# DecadeBox_2.net
KiCad netlist of a schematic drawn in Altium Designer
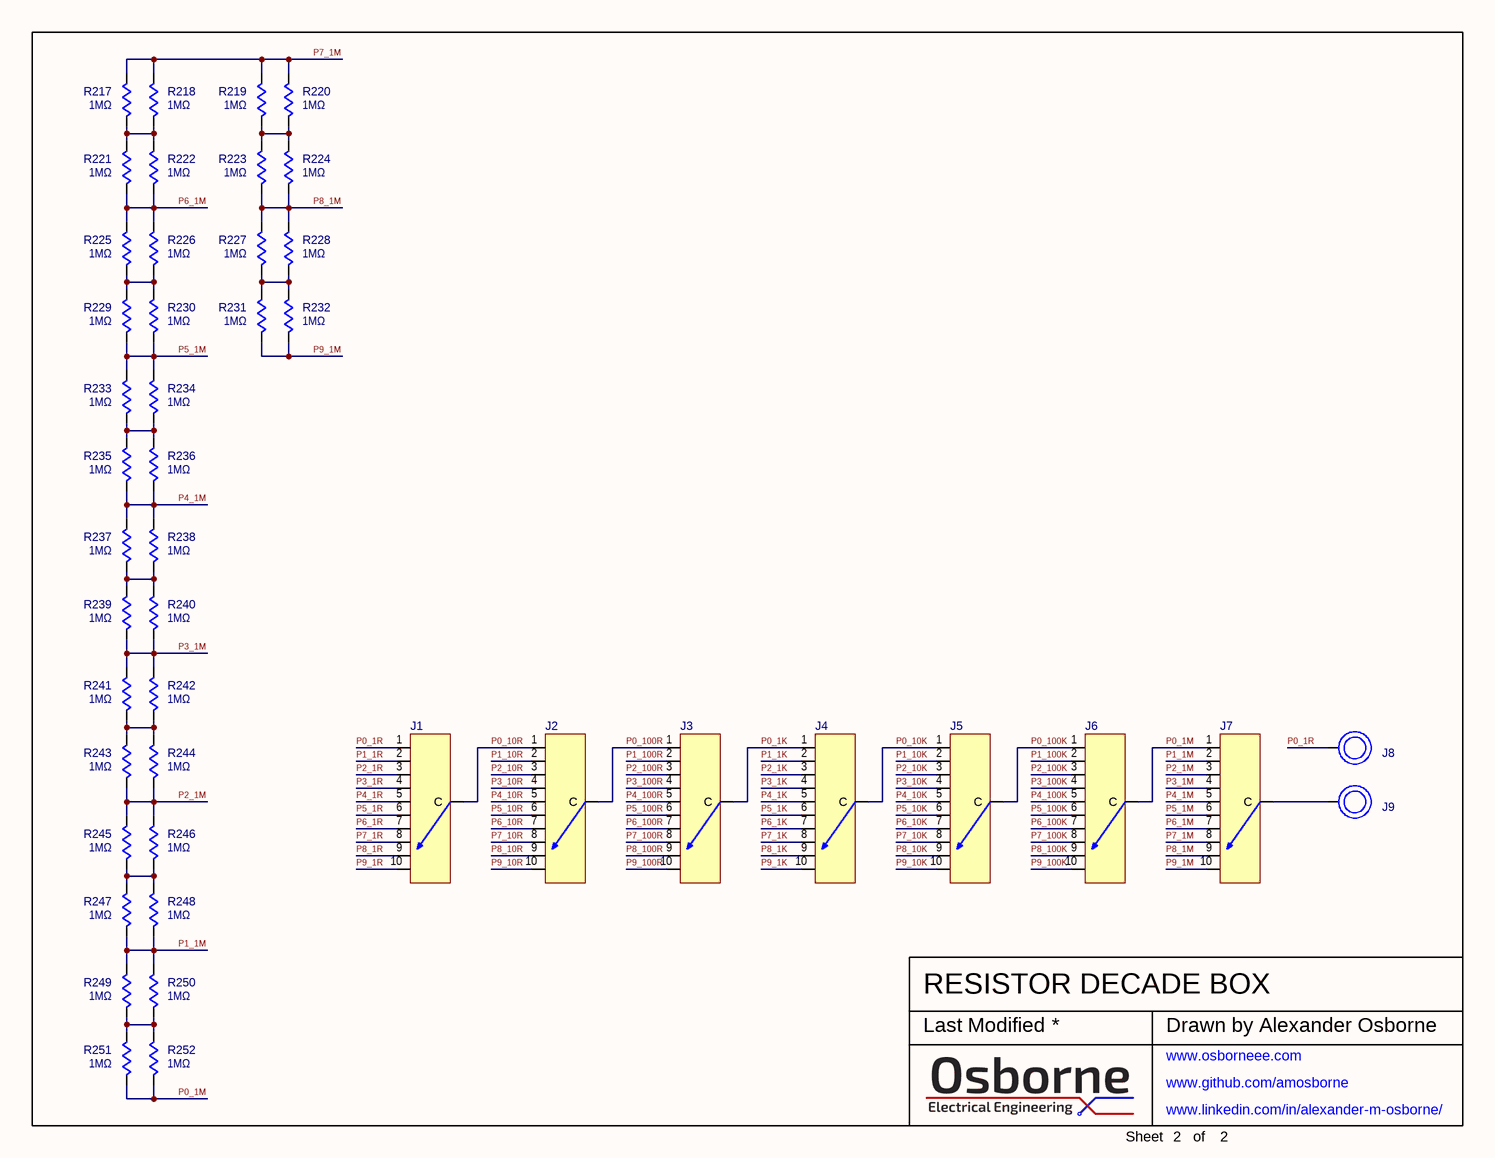
[diagram p0: DecadeBox_2.SchDoc]

(export (version "E")
  (design (tool "Eeschema 10.0.6"))
  (components
    (comp (ref "J1")
      (value "706-56BDP36-01PAJS")
      (footprint "ROTARY")
      (description "10 POLE, SINGLE THROW, ROTARY SWITCH")
      (libsource (lib "DecadeBox") (part "ROTARY"))
    )
    (comp (ref "J2")
      (value "706-56BDP36-01PAJS")
      (footprint "ROTARY")
      (description "10 POLE, SINGLE THROW, ROTARY SWITCH")
      (libsource (lib "DecadeBox") (part "ROTARY"))
    )
    (comp (ref "J3")
      (value "706-56BDP36-01PAJS")
      (footprint "ROTARY")
      (description "10 POLE, SINGLE THROW, ROTARY SWITCH")
      (libsource (lib "DecadeBox") (part "ROTARY"))
    )
    (comp (ref "J4")
      (value "706-56BDP36-01PAJS")
      (footprint "ROTARY")
      (description "10 POLE, SINGLE THROW, ROTARY SWITCH")
      (libsource (lib "DecadeBox") (part "ROTARY"))
    )
    (comp (ref "J5")
      (value "706-56BDP36-01PAJS")
      (footprint "ROTARY")
      (description "10 POLE, SINGLE THROW, ROTARY SWITCH")
      (libsource (lib "DecadeBox") (part "ROTARY"))
    )
    (comp (ref "J6")
      (value "706-56BDP36-01PAJS")
      (footprint "ROTARY")
      (description "10 POLE, SINGLE THROW, ROTARY SWITCH")
      (libsource (lib "DecadeBox") (part "ROTARY"))
    )
    (comp (ref "J7")
      (value "706-56BDP36-01PAJS")
      (footprint "ROTARY")
      (description "10 POLE, SINGLE THROW, ROTARY SWITCH")
      (libsource (lib "DecadeBox") (part "ROTARY"))
    )
    (comp (ref "J8")
      (value "BINDING")
      (description "BINDING POST")
      (libsource (lib "DecadeBox") (part "BINDING"))
    )
    (comp (ref "J9")
      (value "BINDING")
      (description "BINDING POST")
      (libsource (lib "DecadeBox") (part "BINDING"))
    )
    (comp (ref "R217")
      (value "1MΩ")
      (footprint "MRS25")
      (description "RES 1MΩ 1% 50ppm/K 600mW")
      (fields (field (name "TOLERANCE") "1% + 50ppm/K") (field (name "POWER") "600mW"))
      (libsource (lib "DecadeBox") (part "RES-1MOHM"))
    )
    (comp (ref "R218")
      (value "1MΩ")
      (footprint "MRS25")
      (description "RES 1MΩ 1% 50ppm/K 600mW")
      (fields (field (name "TOLERANCE") "1% + 50ppm/K") (field (name "POWER") "600mW"))
      (libsource (lib "DecadeBox") (part "RES-1MOHM"))
    )
    (comp (ref "R219")
      (value "1MΩ")
      (footprint "MRS25")
      (description "RES 1MΩ 1% 50ppm/K 600mW")
      (fields (field (name "TOLERANCE") "1% + 50ppm/K") (field (name "POWER") "600mW"))
      (libsource (lib "DecadeBox") (part "RES-1MOHM"))
    )
    (comp (ref "R220")
      (value "1MΩ")
      (footprint "MRS25")
      (description "RES 1MΩ 1% 50ppm/K 600mW")
      (fields (field (name "TOLERANCE") "1% + 50ppm/K") (field (name "POWER") "600mW"))
      (libsource (lib "DecadeBox") (part "RES-1MOHM"))
    )
    (comp (ref "R221")
      (value "1MΩ")
      (footprint "MRS25")
      (description "RES 1MΩ 1% 50ppm/K 600mW")
      (fields (field (name "TOLERANCE") "1% + 50ppm/K") (field (name "POWER") "600mW"))
      (libsource (lib "DecadeBox") (part "RES-1MOHM"))
    )
    (comp (ref "R222")
      (value "1MΩ")
      (footprint "MRS25")
      (description "RES 1MΩ 1% 50ppm/K 600mW")
      (fields (field (name "TOLERANCE") "1% + 50ppm/K") (field (name "POWER") "600mW"))
      (libsource (lib "DecadeBox") (part "RES-1MOHM"))
    )
    (comp (ref "R223")
      (value "1MΩ")
      (footprint "MRS25")
      (description "RES 1MΩ 1% 50ppm/K 600mW")
      (fields (field (name "TOLERANCE") "1% + 50ppm/K") (field (name "POWER") "600mW"))
      (libsource (lib "DecadeBox") (part "RES-1MOHM"))
    )
    (comp (ref "R224")
      (value "1MΩ")
      (footprint "MRS25")
      (description "RES 1MΩ 1% 50ppm/K 600mW")
      (fields (field (name "TOLERANCE") "1% + 50ppm/K") (field (name "POWER") "600mW"))
      (libsource (lib "DecadeBox") (part "RES-1MOHM"))
    )
    (comp (ref "R225")
      (value "1MΩ")
      (footprint "MRS25")
      (description "RES 1MΩ 1% 50ppm/K 600mW")
      (fields (field (name "TOLERANCE") "1% + 50ppm/K") (field (name "POWER") "600mW"))
      (libsource (lib "DecadeBox") (part "RES-1MOHM"))
    )
    (comp (ref "R226")
      (value "1MΩ")
      (footprint "MRS25")
      (description "RES 1MΩ 1% 50ppm/K 600mW")
      (fields (field (name "TOLERANCE") "1% + 50ppm/K") (field (name "POWER") "600mW"))
      (libsource (lib "DecadeBox") (part "RES-1MOHM"))
    )
    (comp (ref "R227")
      (value "1MΩ")
      (footprint "MRS25")
      (description "RES 1MΩ 1% 50ppm/K 600mW")
      (fields (field (name "TOLERANCE") "1% + 50ppm/K") (field (name "POWER") "600mW"))
      (libsource (lib "DecadeBox") (part "RES-1MOHM"))
    )
    (comp (ref "R228")
      (value "1MΩ")
      (footprint "MRS25")
      (description "RES 1MΩ 1% 50ppm/K 600mW")
      (fields (field (name "TOLERANCE") "1% + 50ppm/K") (field (name "POWER") "600mW"))
      (libsource (lib "DecadeBox") (part "RES-1MOHM"))
    )
    (comp (ref "R229")
      (value "1MΩ")
      (footprint "MRS25")
      (description "RES 1MΩ 1% 50ppm/K 600mW")
      (fields (field (name "TOLERANCE") "1% + 50ppm/K") (field (name "POWER") "600mW"))
      (libsource (lib "DecadeBox") (part "RES-1MOHM"))
    )
    (comp (ref "R230")
      (value "1MΩ")
      (footprint "MRS25")
      (description "RES 1MΩ 1% 50ppm/K 600mW")
      (fields (field (name "TOLERANCE") "1% + 50ppm/K") (field (name "POWER") "600mW"))
      (libsource (lib "DecadeBox") (part "RES-1MOHM"))
    )
    (comp (ref "R231")
      (value "1MΩ")
      (footprint "MRS25")
      (description "RES 1MΩ 1% 50ppm/K 600mW")
      (fields (field (name "TOLERANCE") "1% + 50ppm/K") (field (name "POWER") "600mW"))
      (libsource (lib "DecadeBox") (part "RES-1MOHM"))
    )
    (comp (ref "R232")
      (value "1MΩ")
      (footprint "MRS25")
      (description "RES 1MΩ 1% 50ppm/K 600mW")
      (fields (field (name "TOLERANCE") "1% + 50ppm/K") (field (name "POWER") "600mW"))
      (libsource (lib "DecadeBox") (part "RES-1MOHM"))
    )
    (comp (ref "R233")
      (value "1MΩ")
      (footprint "MRS25")
      (description "RES 1MΩ 1% 50ppm/K 600mW")
      (fields (field (name "TOLERANCE") "1% + 50ppm/K") (field (name "POWER") "600mW"))
      (libsource (lib "DecadeBox") (part "RES-1MOHM"))
    )
    (comp (ref "R234")
      (value "1MΩ")
      (footprint "MRS25")
      (description "RES 1MΩ 1% 50ppm/K 600mW")
      (fields (field (name "TOLERANCE") "1% + 50ppm/K") (field (name "POWER") "600mW"))
      (libsource (lib "DecadeBox") (part "RES-1MOHM"))
    )
    (comp (ref "R235")
      (value "1MΩ")
      (footprint "MRS25")
      (description "RES 1MΩ 1% 50ppm/K 600mW")
      (fields (field (name "TOLERANCE") "1% + 50ppm/K") (field (name "POWER") "600mW"))
      (libsource (lib "DecadeBox") (part "RES-1MOHM"))
    )
    (comp (ref "R236")
      (value "1MΩ")
      (footprint "MRS25")
      (description "RES 1MΩ 1% 50ppm/K 600mW")
      (fields (field (name "TOLERANCE") "1% + 50ppm/K") (field (name "POWER") "600mW"))
      (libsource (lib "DecadeBox") (part "RES-1MOHM"))
    )
    (comp (ref "R237")
      (value "1MΩ")
      (footprint "MRS25")
      (description "RES 1MΩ 1% 50ppm/K 600mW")
      (fields (field (name "TOLERANCE") "1% + 50ppm/K") (field (name "POWER") "600mW"))
      (libsource (lib "DecadeBox") (part "RES-1MOHM"))
    )
    (comp (ref "R238")
      (value "1MΩ")
      (footprint "MRS25")
      (description "RES 1MΩ 1% 50ppm/K 600mW")
      (fields (field (name "TOLERANCE") "1% + 50ppm/K") (field (name "POWER") "600mW"))
      (libsource (lib "DecadeBox") (part "RES-1MOHM"))
    )
    (comp (ref "R239")
      (value "1MΩ")
      (footprint "MRS25")
      (description "RES 1MΩ 1% 50ppm/K 600mW")
      (fields (field (name "TOLERANCE") "1% + 50ppm/K") (field (name "POWER") "600mW"))
      (libsource (lib "DecadeBox") (part "RES-1MOHM"))
    )
    (comp (ref "R240")
      (value "1MΩ")
      (footprint "MRS25")
      (description "RES 1MΩ 1% 50ppm/K 600mW")
      (fields (field (name "TOLERANCE") "1% + 50ppm/K") (field (name "POWER") "600mW"))
      (libsource (lib "DecadeBox") (part "RES-1MOHM"))
    )
    (comp (ref "R241")
      (value "1MΩ")
      (footprint "MRS25")
      (description "RES 1MΩ 1% 50ppm/K 600mW")
      (fields (field (name "TOLERANCE") "1% + 50ppm/K") (field (name "POWER") "600mW"))
      (libsource (lib "DecadeBox") (part "RES-1MOHM"))
    )
    (comp (ref "R242")
      (value "1MΩ")
      (footprint "MRS25")
      (description "RES 1MΩ 1% 50ppm/K 600mW")
      (fields (field (name "TOLERANCE") "1% + 50ppm/K") (field (name "POWER") "600mW"))
      (libsource (lib "DecadeBox") (part "RES-1MOHM"))
    )
    (comp (ref "R243")
      (value "1MΩ")
      (footprint "MRS25")
      (description "RES 1MΩ 1% 50ppm/K 600mW")
      (fields (field (name "TOLERANCE") "1% + 50ppm/K") (field (name "POWER") "600mW"))
      (libsource (lib "DecadeBox") (part "RES-1MOHM"))
    )
    (comp (ref "R244")
      (value "1MΩ")
      (footprint "MRS25")
      (description "RES 1MΩ 1% 50ppm/K 600mW")
      (fields (field (name "TOLERANCE") "1% + 50ppm/K") (field (name "POWER") "600mW"))
      (libsource (lib "DecadeBox") (part "RES-1MOHM"))
    )
    (comp (ref "R245")
      (value "1MΩ")
      (footprint "MRS25")
      (description "RES 1MΩ 1% 50ppm/K 600mW")
      (fields (field (name "TOLERANCE") "1% + 50ppm/K") (field (name "POWER") "600mW"))
      (libsource (lib "DecadeBox") (part "RES-1MOHM"))
    )
    (comp (ref "R246")
      (value "1MΩ")
      (footprint "MRS25")
      (description "RES 1MΩ 1% 50ppm/K 600mW")
      (fields (field (name "TOLERANCE") "1% + 50ppm/K") (field (name "POWER") "600mW"))
      (libsource (lib "DecadeBox") (part "RES-1MOHM"))
    )
    (comp (ref "R247")
      (value "1MΩ")
      (footprint "MRS25")
      (description "RES 1MΩ 1% 50ppm/K 600mW")
      (fields (field (name "TOLERANCE") "1% + 50ppm/K") (field (name "POWER") "600mW"))
      (libsource (lib "DecadeBox") (part "RES-1MOHM"))
    )
    (comp (ref "R248")
      (value "1MΩ")
      (footprint "MRS25")
      (description "RES 1MΩ 1% 50ppm/K 600mW")
      (fields (field (name "TOLERANCE") "1% + 50ppm/K") (field (name "POWER") "600mW"))
      (libsource (lib "DecadeBox") (part "RES-1MOHM"))
    )
    (comp (ref "R249")
      (value "1MΩ")
      (footprint "MRS25")
      (description "RES 1MΩ 1% 50ppm/K 600mW")
      (fields (field (name "TOLERANCE") "1% + 50ppm/K") (field (name "POWER") "600mW"))
      (libsource (lib "DecadeBox") (part "RES-1MOHM"))
    )
    (comp (ref "R250")
      (value "1MΩ")
      (footprint "MRS25")
      (description "RES 1MΩ 1% 50ppm/K 600mW")
      (fields (field (name "TOLERANCE") "1% + 50ppm/K") (field (name "POWER") "600mW"))
      (libsource (lib "DecadeBox") (part "RES-1MOHM"))
    )
    (comp (ref "R251")
      (value "1MΩ")
      (footprint "MRS25")
      (description "RES 1MΩ 1% 50ppm/K 600mW")
      (fields (field (name "TOLERANCE") "1% + 50ppm/K") (field (name "POWER") "600mW"))
      (libsource (lib "DecadeBox") (part "RES-1MOHM"))
    )
    (comp (ref "R252")
      (value "1MΩ")
      (footprint "MRS25")
      (description "RES 1MΩ 1% 50ppm/K 600mW")
      (fields (field (name "TOLERANCE") "1% + 50ppm/K") (field (name "POWER") "600mW"))
      (libsource (lib "DecadeBox") (part "RES-1MOHM"))
    )
  )
  (nets
    (net (code "1") (name "/P0_1K") (class "Default")
      (node (ref "J3") (pin "11") (pinfunction "C_11") (pintype "passive"))
      (node (ref "J4") (pin "1") (pintype "passive"))
    )
    (net (code "2") (name "/P0_1M") (class "Default")
      (node (ref "J6") (pin "11") (pinfunction "C_11") (pintype "passive"))
      (node (ref "J7") (pin "1") (pintype "passive"))
      (node (ref "R251") (pin "2") (pintype "passive"))
      (node (ref "R252") (pin "2") (pintype "passive"))
    )
    (net (code "3") (name "/P0_1R") (class "Default")
      (node (ref "J1") (pin "1") (pintype "passive"))
      (node (ref "J8") (pin "1") (pintype "passive"))
    )
    (net (code "4") (name "/P0_10K") (class "Default")
      (node (ref "J4") (pin "11") (pinfunction "C_11") (pintype "passive"))
      (node (ref "J5") (pin "1") (pintype "passive"))
    )
    (net (code "5") (name "/P0_10R") (class "Default")
      (node (ref "J1") (pin "11") (pinfunction "C_11") (pintype "passive"))
      (node (ref "J2") (pin "1") (pintype "passive"))
    )
    (net (code "6") (name "/P0_100K") (class "Default")
      (node (ref "J5") (pin "11") (pinfunction "C_11") (pintype "passive"))
      (node (ref "J6") (pin "1") (pintype "passive"))
    )
    (net (code "7") (name "/P0_100R") (class "Default")
      (node (ref "J2") (pin "11") (pinfunction "C_11") (pintype "passive"))
      (node (ref "J3") (pin "1") (pintype "passive"))
    )
    (net (code "8") (name "/P1_1K") (class "Default") (node (ref "J4") (pin "2") (pintype "passive")))
    (net (code "9") (name "/P1_1M") (class "Default")
      (node (ref "J7") (pin "2") (pintype "passive"))
      (node (ref "R247") (pin "2") (pintype "passive"))
      (node (ref "R248") (pin "2") (pintype "passive"))
      (node (ref "R249") (pin "1") (pintype "passive"))
      (node (ref "R250") (pin "1") (pintype "passive"))
    )
    (net (code "10") (name "/P1_1R") (class "Default") (node (ref "J1") (pin "2") (pintype "passive")))
    (net (code "11") (name "/P1_10K") (class "Default") (node (ref "J5") (pin "2") (pintype "passive")))
    (net (code "12") (name "/P1_10R") (class "Default") (node (ref "J2") (pin "2") (pintype "passive")))
    (net (code "13") (name "/P1_100K") (class "Default") (node (ref "J6") (pin "2") (pintype "passive")))
    (net (code "14") (name "/P1_100R") (class "Default") (node (ref "J3") (pin "2") (pintype "passive")))
    (net (code "15") (name "/P2_1K") (class "Default") (node (ref "J4") (pin "3") (pintype "passive")))
    (net (code "16") (name "/P2_1M") (class "Default")
      (node (ref "J7") (pin "3") (pintype "passive"))
      (node (ref "R243") (pin "2") (pintype "passive"))
      (node (ref "R244") (pin "2") (pintype "passive"))
      (node (ref "R245") (pin "1") (pintype "passive"))
      (node (ref "R246") (pin "1") (pintype "passive"))
    )
    (net (code "17") (name "/P2_1R") (class "Default") (node (ref "J1") (pin "3") (pintype "passive")))
    (net (code "18") (name "/P2_10K") (class "Default") (node (ref "J5") (pin "3") (pintype "passive")))
    (net (code "19") (name "/P2_10R") (class "Default") (node (ref "J2") (pin "3") (pintype "passive")))
    (net (code "20") (name "/P2_100K") (class "Default") (node (ref "J6") (pin "3") (pintype "passive")))
    (net (code "21") (name "/P2_100R") (class "Default") (node (ref "J3") (pin "3") (pintype "passive")))
    (net (code "22") (name "/P3_1K") (class "Default") (node (ref "J4") (pin "4") (pintype "passive")))
    (net (code "23") (name "/P3_1M") (class "Default")
      (node (ref "J7") (pin "4") (pintype "passive"))
      (node (ref "R239") (pin "2") (pintype "passive"))
      (node (ref "R240") (pin "2") (pintype "passive"))
      (node (ref "R241") (pin "1") (pintype "passive"))
      (node (ref "R242") (pin "1") (pintype "passive"))
    )
    (net (code "24") (name "/P3_1R") (class "Default") (node (ref "J1") (pin "4") (pintype "passive")))
    (net (code "25") (name "/P3_10K") (class "Default") (node (ref "J5") (pin "4") (pintype "passive")))
    (net (code "26") (name "/P3_10R") (class "Default") (node (ref "J2") (pin "4") (pintype "passive")))
    (net (code "27") (name "/P3_100K") (class "Default") (node (ref "J6") (pin "4") (pintype "passive")))
    (net (code "28") (name "/P3_100R") (class "Default") (node (ref "J3") (pin "4") (pintype "passive")))
    (net (code "29") (name "/P4_1K") (class "Default") (node (ref "J4") (pin "5") (pintype "passive")))
    (net (code "30") (name "/P4_1M") (class "Default")
      (node (ref "J7") (pin "5") (pintype "passive"))
      (node (ref "R235") (pin "2") (pintype "passive"))
      (node (ref "R236") (pin "2") (pintype "passive"))
      (node (ref "R237") (pin "1") (pintype "passive"))
      (node (ref "R238") (pin "1") (pintype "passive"))
    )
    (net (code "31") (name "/P4_1R") (class "Default") (node (ref "J1") (pin "5") (pintype "passive")))
    (net (code "32") (name "/P4_10K") (class "Default") (node (ref "J5") (pin "5") (pintype "passive")))
    (net (code "33") (name "/P4_10R") (class "Default") (node (ref "J2") (pin "5") (pintype "passive")))
    (net (code "34") (name "/P4_100K") (class "Default") (node (ref "J6") (pin "5") (pintype "passive")))
    (net (code "35") (name "/P4_100R") (class "Default") (node (ref "J3") (pin "5") (pintype "passive")))
    (net (code "36") (name "/P5_1K") (class "Default") (node (ref "J4") (pin "6") (pintype "passive")))
    (net (code "37") (name "/P5_1M") (class "Default")
      (node (ref "J7") (pin "6") (pintype "passive"))
      (node (ref "R229") (pin "2") (pintype "passive"))
      (node (ref "R230") (pin "2") (pintype "passive"))
      (node (ref "R233") (pin "1") (pintype "passive"))
      (node (ref "R234") (pin "1") (pintype "passive"))
    )
    (net (code "38") (name "/P5_1R") (class "Default") (node (ref "J1") (pin "6") (pintype "passive")))
    (net (code "39") (name "/P5_10K") (class "Default") (node (ref "J5") (pin "6") (pintype "passive")))
    (net (code "40") (name "/P5_10R") (class "Default") (node (ref "J2") (pin "6") (pintype "passive")))
    (net (code "41") (name "/P5_100K") (class "Default") (node (ref "J6") (pin "6") (pintype "passive")))
    (net (code "42") (name "/P5_100R") (class "Default") (node (ref "J3") (pin "6") (pintype "passive")))
    (net (code "43") (name "/P6_1K") (class "Default") (node (ref "J4") (pin "7") (pintype "passive")))
    (net (code "44") (name "/P6_1M") (class "Default")
      (node (ref "J7") (pin "7") (pintype "passive"))
      (node (ref "R221") (pin "2") (pintype "passive"))
      (node (ref "R222") (pin "2") (pintype "passive"))
      (node (ref "R225") (pin "1") (pintype "passive"))
      (node (ref "R226") (pin "1") (pintype "passive"))
    )
    (net (code "45") (name "/P6_1R") (class "Default") (node (ref "J1") (pin "7") (pintype "passive")))
    (net (code "46") (name "/P6_10K") (class "Default") (node (ref "J5") (pin "7") (pintype "passive")))
    (net (code "47") (name "/P6_10R") (class "Default") (node (ref "J2") (pin "7") (pintype "passive")))
    (net (code "48") (name "/P6_100K") (class "Default") (node (ref "J6") (pin "7") (pintype "passive")))
    (net (code "49") (name "/P6_100R") (class "Default") (node (ref "J3") (pin "7") (pintype "passive")))
    (net (code "50") (name "/P7_1K") (class "Default") (node (ref "J4") (pin "8") (pintype "passive")))
    (net (code "51") (name "/P7_1M") (class "Default")
      (node (ref "J7") (pin "8") (pintype "passive"))
      (node (ref "R217") (pin "1") (pintype "passive"))
      (node (ref "R218") (pin "1") (pintype "passive"))
      (node (ref "R219") (pin "1") (pintype "passive"))
      (node (ref "R220") (pin "1") (pintype "passive"))
    )
    (net (code "52") (name "/P7_1R") (class "Default") (node (ref "J1") (pin "8") (pintype "passive")))
    (net (code "53") (name "/P7_10K") (class "Default") (node (ref "J5") (pin "8") (pintype "passive")))
    (net (code "54") (name "/P7_10R") (class "Default") (node (ref "J2") (pin "8") (pintype "passive")))
    (net (code "55") (name "/P7_100K") (class "Default") (node (ref "J6") (pin "8") (pintype "passive")))
    (net (code "56") (name "/P7_100R") (class "Default") (node (ref "J3") (pin "8") (pintype "passive")))
    (net (code "57") (name "/P8_1K") (class "Default") (node (ref "J4") (pin "9") (pintype "passive")))
    (net (code "58") (name "/P8_1M") (class "Default")
      (node (ref "J7") (pin "9") (pintype "passive"))
      (node (ref "R223") (pin "2") (pintype "passive"))
      (node (ref "R224") (pin "2") (pintype "passive"))
      (node (ref "R227") (pin "1") (pintype "passive"))
      (node (ref "R228") (pin "1") (pintype "passive"))
    )
    (net (code "59") (name "/P8_1R") (class "Default") (node (ref "J1") (pin "9") (pintype "passive")))
    (net (code "60") (name "/P8_10K") (class "Default") (node (ref "J5") (pin "9") (pintype "passive")))
    (net (code "61") (name "/P8_10R") (class "Default") (node (ref "J2") (pin "9") (pintype "passive")))
    (net (code "62") (name "/P8_100K") (class "Default") (node (ref "J6") (pin "9") (pintype "passive")))
    (net (code "63") (name "/P8_100R") (class "Default") (node (ref "J3") (pin "9") (pintype "passive")))
    (net (code "64") (name "/P9_1K") (class "Default") (node (ref "J4") (pin "10") (pintype "passive")))
    (net (code "65") (name "/P9_1M") (class "Default")
      (node (ref "J7") (pin "10") (pintype "passive"))
      (node (ref "R231") (pin "2") (pintype "passive"))
      (node (ref "R232") (pin "2") (pintype "passive"))
    )
    (net (code "66") (name "/P9_1R") (class "Default") (node (ref "J1") (pin "10") (pintype "passive")))
    (net (code "67") (name "/P9_10K") (class "Default") (node (ref "J5") (pin "10") (pintype "passive")))
    (net (code "68") (name "/P9_10R") (class "Default") (node (ref "J2") (pin "10") (pintype "passive")))
    (net (code "69") (name "/P9_100K") (class "Default") (node (ref "J6") (pin "10") (pintype "passive")))
    (net (code "70") (name "/P9_100R") (class "Default") (node (ref "J3") (pin "10") (pintype "passive")))
    (net (code "71") (name "Net-(J7-C)") (class "Default")
      (node (ref "J7") (pin "11") (pinfunction "C_11") (pintype "passive"))
      (node (ref "J9") (pin "1") (pintype "passive"))
    )
    (net (code "72") (name "Net-(R217-Pad2)") (class "Default")
      (node (ref "R217") (pin "2") (pintype "passive"))
      (node (ref "R218") (pin "2") (pintype "passive"))
      (node (ref "R221") (pin "1") (pintype "passive"))
      (node (ref "R222") (pin "1") (pintype "passive"))
    )
    (net (code "73") (name "Net-(R219-Pad2)") (class "Default")
      (node (ref "R219") (pin "2") (pintype "passive"))
      (node (ref "R220") (pin "2") (pintype "passive"))
      (node (ref "R223") (pin "1") (pintype "passive"))
      (node (ref "R224") (pin "1") (pintype "passive"))
    )
    (net (code "74") (name "Net-(R225-Pad2)") (class "Default")
      (node (ref "R225") (pin "2") (pintype "passive"))
      (node (ref "R226") (pin "2") (pintype "passive"))
      (node (ref "R229") (pin "1") (pintype "passive"))
      (node (ref "R230") (pin "1") (pintype "passive"))
    )
    (net (code "75") (name "Net-(R227-Pad2)") (class "Default")
      (node (ref "R227") (pin "2") (pintype "passive"))
      (node (ref "R228") (pin "2") (pintype "passive"))
      (node (ref "R231") (pin "1") (pintype "passive"))
      (node (ref "R232") (pin "1") (pintype "passive"))
    )
    (net (code "76") (name "Net-(R233-Pad2)") (class "Default")
      (node (ref "R233") (pin "2") (pintype "passive"))
      (node (ref "R234") (pin "2") (pintype "passive"))
      (node (ref "R235") (pin "1") (pintype "passive"))
      (node (ref "R236") (pin "1") (pintype "passive"))
    )
    (net (code "77") (name "Net-(R237-Pad2)") (class "Default")
      (node (ref "R237") (pin "2") (pintype "passive"))
      (node (ref "R238") (pin "2") (pintype "passive"))
      (node (ref "R239") (pin "1") (pintype "passive"))
      (node (ref "R240") (pin "1") (pintype "passive"))
    )
    (net (code "78") (name "Net-(R241-Pad2)") (class "Default")
      (node (ref "R241") (pin "2") (pintype "passive"))
      (node (ref "R242") (pin "2") (pintype "passive"))
      (node (ref "R243") (pin "1") (pintype "passive"))
      (node (ref "R244") (pin "1") (pintype "passive"))
    )
    (net (code "79") (name "Net-(R245-Pad2)") (class "Default")
      (node (ref "R245") (pin "2") (pintype "passive"))
      (node (ref "R246") (pin "2") (pintype "passive"))
      (node (ref "R247") (pin "1") (pintype "passive"))
      (node (ref "R248") (pin "1") (pintype "passive"))
    )
    (net (code "80") (name "Net-(R249-Pad2)") (class "Default")
      (node (ref "R249") (pin "2") (pintype "passive"))
      (node (ref "R250") (pin "2") (pintype "passive"))
      (node (ref "R251") (pin "1") (pintype "passive"))
      (node (ref "R252") (pin "1") (pintype "passive"))
    )
  )
)
